# Sheet1.net
KiCad netlist of a schematic drawn in Altium Designer
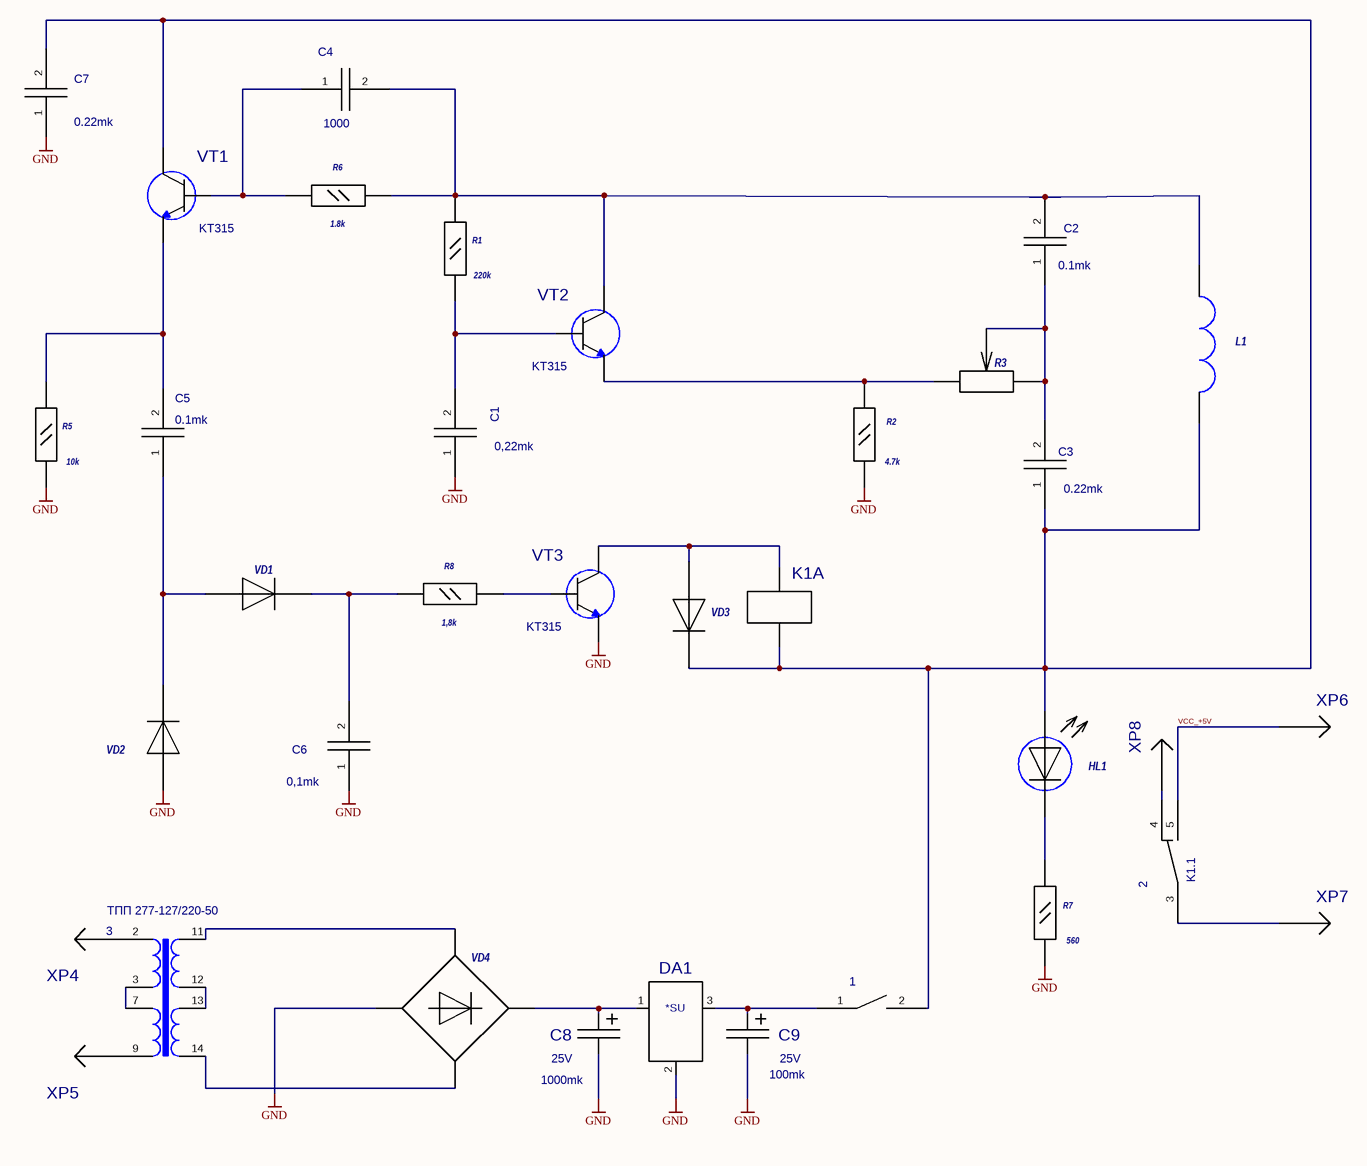
[diagram p0: Sheet1.SCHDOC]

(export (version "E")
  (design (tool "Eeschema 10.0.6"))
  (components
    (comp (ref "1") (value "T1") (footprint "T1") (libsource (lib "*") (part "T1")))
    (comp (ref "2") (value "K1.1") (footprint "K1.1") (libsource (lib "*") (part "K1.1")))
    (comp (ref "3")
      (value "ТПП 277-127/220-50")
      (footprint "ТПП 277-127/220-50")
      (libsource (lib "*") (part "ТПП 277-127/220-50"))
    )
    (comp (ref "C1")
      (value "0,22mk")
      (footprint "KM6A - M47")
      (description "25")
      (libsource (lib "*") (part "25"))
    )
    (comp (ref "C2")
      (value "0.1mk")
      (footprint "KM6A - M47")
      (description "25")
      (libsource (lib "*") (part "25"))
    )
    (comp (ref "C3")
      (value "0.22mk")
      (footprint "KM6A - M47")
      (description "25")
      (libsource (lib "*") (part "25"))
    )
    (comp (ref "C4")
      (value "1000")
      (footprint "KM6A - M47")
      (description "25")
      (libsource (lib "*") (part "25"))
    )
    (comp (ref "C5")
      (value "0.1mk")
      (footprint "KM6A - M47")
      (description "25")
      (libsource (lib "*") (part "25"))
    )
    (comp (ref "C6")
      (value "0,1mk")
      (footprint "KM6A - M47")
      (description "25")
      (libsource (lib "*") (part "25"))
    )
    (comp (ref "C7")
      (value "0.22mk")
      (footprint "KM6A - M47")
      (description "25")
      (libsource (lib "*") (part "25"))
    )
    (comp (ref "C8")
      (value "25V")
      (footprint "K534A-1")
      (description "K534A-1")
      (libsource (lib "*") (part "K534A-1"))
    )
    (comp (ref "C9")
      (value "25V")
      (footprint "K534A-1")
      (description "K534A-1")
      (libsource (lib "*") (part "K534A-1"))
    )
    (comp (ref "DA1") (value "KR142EN") (footprint "KR142EN") (libsource (lib "*") (part "KR142EN")))
    (comp (ref "HL1") (value "АЛ307") (footprint "АЛ307") (libsource (lib "*") (part "АЛ307")))
    (comp (ref "K1") (value "РЭС-64") (footprint "RES64") (libsource (lib "Lab3") (part "РЭС-64")))
    (comp (ref "L1") (value "L (3,5)") (footprint "L (3,5)") (libsource (lib "*") (part "L (3,5)")))
    (comp (ref "R1")
      (value "220k")
      (footprint "МЛТ(0.125)")
      (description "МЛТ(0.125)")
      (libsource (lib "*") (part "МЛТ(0.125)"))
    )
    (comp (ref "R2")
      (value "4.7k")
      (footprint "МЛТ(0.125)")
      (description "МЛТ(0.125)")
      (libsource (lib "*") (part "МЛТ(0.125)"))
    )
    (comp (ref "R3") (value "СП3-38В") (footprint "СП3-38В") (libsource (lib "*") (part "СП3-38В")))
    (comp (ref "R5")
      (value "10k")
      (footprint "МЛТ(0.125)")
      (description "МЛТ(0.125)")
      (libsource (lib "*") (part "МЛТ(0.125)"))
    )
    (comp (ref "R6")
      (value "1.8k")
      (footprint "МЛТ(0.125)")
      (description "МЛТ(0.125)")
      (libsource (lib "*") (part "МЛТ(0.125)"))
    )
    (comp (ref "R7")
      (value "560")
      (footprint "МЛТ(0.125)")
      (description "МЛТ(0.125)")
      (libsource (lib "*") (part "МЛТ(0.125)"))
    )
    (comp (ref "R8")
      (value "1,8k")
      (footprint "МЛТ(0.125)")
      (description "МЛТ(0.125)")
      (libsource (lib "*") (part "МЛТ(0.125)"))
    )
    (comp (ref "VD1") (value "КД522Б") (footprint "КД522") (libsource (lib "*") (part "КД522Б")))
    (comp (ref "VD2") (value "КД522Б") (footprint "КД522") (libsource (lib "*") (part "КД522Б")))
    (comp (ref "VD3") (value "КД522Б") (footprint "КД522") (libsource (lib "*") (part "КД522Б")))
    (comp (ref "VD4") (value "КЦ407") (footprint "КЦ407") (libsource (lib "*") (part "КЦ407")))
    (comp (ref "VT1") (value "KT315") (footprint "KT-13") (libsource (lib "*") (part "KT315")))
    (comp (ref "VT2") (value "KT315") (footprint "KT-13") (libsource (lib "*") (part "KT315")))
    (comp (ref "VT3") (value "KT315") (footprint "KT-13") (libsource (lib "*") (part "KT315")))
    (comp (ref "XP4") (value "XP1") (footprint "PAD") (libsource (lib "*") (part "XP1")))
    (comp (ref "XP5") (value "XP1") (footprint "PAD") (libsource (lib "*") (part "XP1")))
    (comp (ref "XP6") (value "XP1") (footprint "PAD") (libsource (lib "*") (part "XP1")))
    (comp (ref "XP7") (value "XP1") (footprint "PAD") (libsource (lib "*") (part "XP1")))
    (comp (ref "XP8") (value "XP1") (footprint "PAD") (libsource (lib "*") (part "XP1")))
  )
  (nets
    (net (code "1") (name "/VCC_+5V") (class "Default")
      (node (ref "2") (pin "5") (pinfunction "5_5") (pintype "passive"))
      (node (ref "XP6") (pin "1") (pinfunction "A1_1") (pintype "passive"))
    )
    (net (code "2") (name "GND") (class "Default")
      (node (ref "C1") (pin "1") (pinfunction "1_1") (pintype "passive"))
      (node (ref "C6") (pin "1") (pinfunction "1_1") (pintype "passive"))
      (node (ref "C7") (pin "1") (pinfunction "1_1") (pintype "passive"))
      (node (ref "C8") (pin "2") (pinfunction "I/OB_2") (pintype "passive"))
      (node (ref "C9") (pin "2") (pinfunction "I/OB_2") (pintype "passive"))
      (node (ref "DA1") (pin "2") (pinfunction "GND0_2") (pintype "passive"))
      (node (ref "R2") (pin "1") (pinfunction "1_1") (pintype "passive"))
      (node (ref "R5") (pin "1") (pinfunction "1_1") (pintype "passive"))
      (node (ref "R7") (pin "1") (pinfunction "1_1") (pintype "passive"))
      (node (ref "VD2") (pin "1") (pinfunction "1_1") (pintype "passive"))
      (node (ref "VD4") (pin "1") (pinfunction "1_1") (pintype "passive"))
      (node (ref "VT3") (pin "1") (pinfunction "E_1") (pintype "passive"))
    )
    (net (code "3") (name "Net-(3-Pad3)") (class "Default")
      (node (ref "3") (pin "3") (pinfunction "3_3") (pintype "passive"))
      (node (ref "3") (pin "7") (pinfunction "7_7") (pintype "passive"))
    )
    (net (code "4") (name "Net-(3-Pad11)") (class "Default")
      (node (ref "3") (pin "11") (pinfunction "11_11") (pintype "passive"))
      (node (ref "VD4") (pin "2") (pinfunction "2_2") (pintype "passive"))
    )
    (net (code "5") (name "Net-(3-Pad12)") (class "Default")
      (node (ref "3") (pin "12") (pinfunction "12_12") (pintype "passive"))
      (node (ref "3") (pin "13") (pinfunction "13_13") (pintype "passive"))
    )
    (net (code "6") (name "Net-(C2-Pad1)") (class "Default")
      (node (ref "C2") (pin "1") (pinfunction "1_1") (pintype "passive"))
      (node (ref "C3") (pin "2") (pinfunction "2_2") (pintype "passive"))
      (node (ref "R3") (pin "2") (pinfunction "2_2") (pintype "passive"))
      (node (ref "R3") (pin "3") (pinfunction "3_3") (pintype "passive"))
    )
    (net (code "7") (name "Net-(C5-Pad1)") (class "Default")
      (node (ref "C5") (pin "1") (pinfunction "1_1") (pintype "passive"))
      (node (ref "VD1") (pin "1") (pinfunction "1_1") (pintype "passive"))
      (node (ref "VD2") (pin "2") (pinfunction "2_2") (pintype "passive"))
    )
    (net (code "8") (name "Net-(C6-Pad2)") (class "Default")
      (node (ref "C6") (pin "2") (pinfunction "2_2") (pintype "passive"))
      (node (ref "R8") (pin "2") (pinfunction "2_2") (pintype "passive"))
      (node (ref "VD1") (pin "2") (pinfunction "2_2") (pintype "passive"))
    )
    (net (code "9") (name "Net-(C8-I{slash}OA)") (class "Default")
      (node (ref "C8") (pin "1") (pinfunction "I/OA_1") (pintype "passive"))
      (node (ref "DA1") (pin "1") (pinfunction "IN0_1") (pintype "passive"))
      (node (ref "VD4") (pin "3") (pinfunction "3_3") (pintype "passive"))
    )
    (net (code "10") (name "Net-(C9-I{slash}OA)") (class "Default")
      (node (ref "1") (pin "1") (pinfunction "1_1") (pintype "passive"))
      (node (ref "C9") (pin "1") (pinfunction "I/OA_1") (pintype "passive"))
      (node (ref "DA1") (pin "3") (pinfunction "OUT0_3") (pintype "passive"))
    )
    (net (code "11") (name "Net-(HL1-Pad2)") (class "Default")
      (node (ref "HL1") (pin "2") (pinfunction "2_2") (pintype "passive"))
      (node (ref "R7") (pin "2") (pinfunction "2_2") (pintype "passive"))
    )
    (net (code "12") (name "Net-(K1-I{slash}O1)") (class "Default")
      (node (ref "1") (pin "2") (pinfunction "2_2") (pintype "passive"))
      (node (ref "C3") (pin "1") (pinfunction "1_1") (pintype "passive"))
      (node (ref "C7") (pin "2") (pinfunction "2_2") (pintype "passive"))
      (node (ref "HL1") (pin "1") (pinfunction "1_1") (pintype "passive"))
      (node (ref "K1") (pin "1") (pinfunction "I/O1_1") (pintype "passive"))
      (node (ref "L1") (pin "2") (pinfunction "2_2") (pintype "passive"))
      (node (ref "VD3") (pin "2") (pinfunction "2_2") (pintype "passive"))
      (node (ref "VT1") (pin "2") (pinfunction "K_2") (pintype "passive"))
    )
    (net (code "13") (name "Net-(K1-I{slash}O2)") (class "Default")
      (node (ref "K1") (pin "2") (pinfunction "I/O2_2") (pintype "passive"))
      (node (ref "VD3") (pin "1") (pinfunction "1_1") (pintype "passive"))
      (node (ref "VT3") (pin "2") (pinfunction "K_2") (pintype "passive"))
    )
    (net (code "14") (name "Net-(VD4-4)") (class "Default")
      (node (ref "3") (pin "14") (pinfunction "14_14") (pintype "passive"))
      (node (ref "VD4") (pin "5") (pinfunction "4_5") (pintype "passive"))
    )
    (net (code "15") (name "Net-(VT1-B)") (class "Default")
      (node (ref "C4") (pin "1") (pinfunction "1_1") (pintype "passive"))
      (node (ref "R6") (pin "2") (pinfunction "2_2") (pintype "passive"))
      (node (ref "VT1") (pin "3") (pinfunction "B_3") (pintype "passive"))
    )
    (net (code "16") (name "Net-(VT1-E)") (class "Default")
      (node (ref "C5") (pin "2") (pinfunction "2_2") (pintype "passive"))
      (node (ref "R5") (pin "2") (pinfunction "2_2") (pintype "passive"))
      (node (ref "VT1") (pin "1") (pinfunction "E_1") (pintype "passive"))
    )
    (net (code "17") (name "Net-(VT2-B)") (class "Default")
      (node (ref "C1") (pin "2") (pinfunction "2_2") (pintype "passive"))
      (node (ref "R1") (pin "1") (pinfunction "1_1") (pintype "passive"))
      (node (ref "VT2") (pin "3") (pinfunction "B_3") (pintype "passive"))
    )
    (net (code "18") (name "Net-(VT2-E)") (class "Default")
      (node (ref "R2") (pin "2") (pinfunction "2_2") (pintype "passive"))
      (node (ref "R3") (pin "1") (pinfunction "1_1") (pintype "passive"))
      (node (ref "VT2") (pin "1") (pinfunction "E_1") (pintype "passive"))
    )
    (net (code "19") (name "Net-(VT2-K)") (class "Default")
      (node (ref "C2") (pin "2") (pinfunction "2_2") (pintype "passive"))
      (node (ref "C4") (pin "2") (pinfunction "2_2") (pintype "passive"))
      (node (ref "L1") (pin "1") (pinfunction "1_1") (pintype "passive"))
      (node (ref "R1") (pin "2") (pinfunction "2_2") (pintype "passive"))
      (node (ref "R6") (pin "1") (pinfunction "1_1") (pintype "passive"))
      (node (ref "VT2") (pin "2") (pinfunction "K_2") (pintype "passive"))
    )
    (net (code "20") (name "Net-(VT3-B)") (class "Default")
      (node (ref "R8") (pin "1") (pinfunction "1_1") (pintype "passive"))
      (node (ref "VT3") (pin "3") (pinfunction "B_3") (pintype "passive"))
    )
    (net (code "21") (name "Net-(XP4-A1)") (class "Default")
      (node (ref "3") (pin "2") (pinfunction "2_2") (pintype "passive"))
      (node (ref "XP4") (pin "1") (pinfunction "A1_1") (pintype "passive"))
    )
    (net (code "22") (name "Net-(XP5-A1)") (class "Default")
      (node (ref "3") (pin "9") (pinfunction "9_9") (pintype "passive"))
      (node (ref "XP5") (pin "1") (pinfunction "A1_1") (pintype "passive"))
    )
    (net (code "23") (name "Net-(XP7-A1)") (class "Default")
      (node (ref "2") (pin "3") (pinfunction "3_3") (pintype "passive"))
      (node (ref "XP7") (pin "1") (pinfunction "A1_1") (pintype "passive"))
    )
    (net (code "24") (name "Net-(XP8-A1)") (class "Default")
      (node (ref "2") (pin "4") (pinfunction "4_4") (pintype "passive"))
      (node (ref "XP8") (pin "1") (pinfunction "A1_1") (pintype "passive"))
    )
    (net (code "25") (name "unconnected-(K1-Pad5)") (class "Default")
      (node (ref "K1") (pin "5") (pintype "passive"))
    )
    (net (code "26") (name "unconnected-(VD4-Pad4)") (class "Default")
      (node (ref "VD4") (pin "4") (pintype "passive"))
    )
    (net (code "27") (name "unconnected-(VD4-Pad6)") (class "Default")
      (node (ref "VD4") (pin "6") (pintype "passive"))
    )
  )
)
